# MasterNode.net
KiCad netlist of a schematic drawn in EAGLE
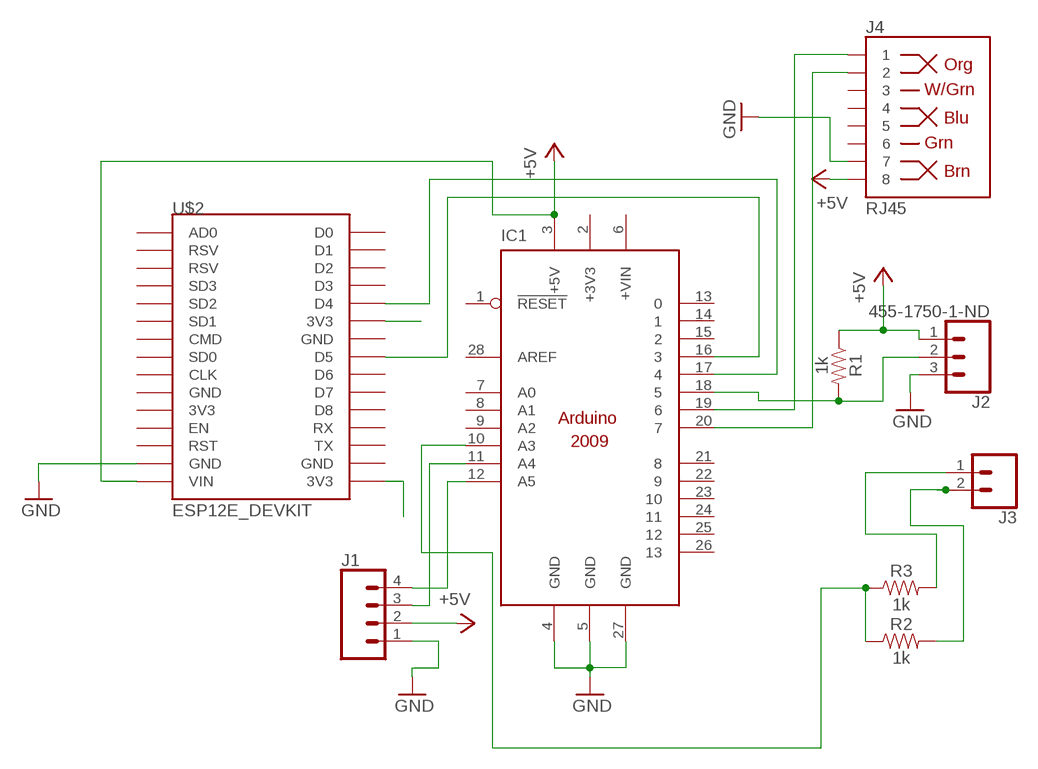
[diagram p0: schematic, sheet 1]

(export (version "E")
  (design (tool "Eeschema 10.0.6"))
  (components
    (comp (ref "IC1")
      (value "ARDUINO2009_10")
      (footprint "eagle-import:ARDUINO2009")
      (libsource (lib "eagle-import") (part "ARDUINO2009_10"))
    )
    (comp (ref "J1")
      (value "CONN_04PTH")
      (footprint "eagle-import:1X04")
      (libsource (lib "eagle-import") (part "CONN_04PTH"))
    )
    (comp (ref "J2")
      (value "455-1750-1-ND")
      (footprint "eagle-import:1X03")
      (libsource (lib "eagle-import") (part "CONN_03"))
    )
    (comp (ref "J3")
      (value "CONN_02")
      (footprint "eagle-import:1X02")
      (libsource (lib "eagle-import") (part "CONN_02"))
    )
    (comp (ref "J4")
      (value "RJ45")
      (footprint "eagle-import:RJ45-8")
      (libsource (lib "eagle-import") (part "RJ45-8"))
    )
    (comp (ref "R1")
      (value "1k")
      (footprint "eagle-import:AXIAL-0.3")
      (libsource (lib "eagle-import") (part "1KOHM-HORIZ-1/4W-5%"))
    )
    (comp (ref "R2")
      (value "1k")
      (footprint "eagle-import:AXIAL-0.3")
      (libsource (lib "eagle-import") (part "1KOHM-HORIZ-1/4W-5%"))
    )
    (comp (ref "R3")
      (value "1k")
      (footprint "eagle-import:AXIAL-0.3")
      (libsource (lib "eagle-import") (part "1KOHM-HORIZ-1/4W-5%"))
    )
    (comp (ref "U$2")
      (value "ESP12E_DEVKIT")
      (footprint "eagle-import:ESP12E_DEVKIT")
      (libsource (lib "eagle-import") (part "ESP12E_DEVKIT"))
    )
  )
  (nets
    (net (code "1") (name "+5V") (class "Default")
      (node (ref "IC1") (pin "3") (pinfunction "+5V_3") (pintype "power_in"))
      (node (ref "J1") (pin "2") (pinfunction "2_2") (pintype "passive"))
      (node (ref "J2") (pin "1") (pinfunction "1_1") (pintype "passive"))
      (node (ref "J4") (pin "8") (pinfunction "8_8") (pintype "bidirectional"))
      (node (ref "R1") (pin "P$1") (pinfunction "1_P$1") (pintype "passive"))
      (node (ref "U$2") (pin "VIN") (pinfunction "VIN_VIN") (pintype "bidirectional"))
    )
    (net (code "2") (name "/+3V3") (class "Default")
      (node (ref "IC1") (pin "2") (pinfunction "+3V3_2") (pintype "power_in"))
    )
    (net (code "3") (name "GND") (class "Default")
      (node (ref "IC1") (pin "27") (pinfunction "GND_27") (pintype "power_in"))
      (node (ref "IC1") (pin "4") (pinfunction "GND_4") (pintype "power_in"))
      (node (ref "IC1") (pin "5") (pinfunction "GND_5") (pintype "power_in"))
      (node (ref "J1") (pin "1") (pinfunction "1_1") (pintype "passive"))
      (node (ref "J2") (pin "3") (pinfunction "3_3") (pintype "passive"))
      (node (ref "J4") (pin "7") (pinfunction "7_7") (pintype "bidirectional"))
      (node (ref "U$2") (pin "GND@1") (pinfunction "GND_GND@1") (pintype "bidirectional"))
    )
    (net (code "4") (name "Net-(IC1-3)") (class "Default")
      (node (ref "IC1") (pin "16") (pinfunction "3_16") (pintype "bidirectional"))
      (node (ref "U$2") (pin "D5") (pinfunction "D5_D5") (pintype "bidirectional"))
    )
    (net (code "5") (name "Net-(IC1-4)") (class "Default")
      (node (ref "IC1") (pin "17") (pinfunction "4_17") (pintype "bidirectional"))
      (node (ref "U$2") (pin "D4") (pinfunction "D4_D4") (pintype "bidirectional"))
    )
    (net (code "6") (name "Net-(IC1-5)") (class "Default")
      (node (ref "IC1") (pin "18") (pinfunction "5_18") (pintype "bidirectional"))
      (node (ref "J2") (pin "2") (pinfunction "2_2") (pintype "passive"))
      (node (ref "R1") (pin "P$2") (pinfunction "2_P$2") (pintype "passive"))
    )
    (net (code "7") (name "Net-(IC1-6)") (class "Default")
      (node (ref "IC1") (pin "19") (pinfunction "6_19") (pintype "bidirectional"))
      (node (ref "J4") (pin "1") (pinfunction "1_1") (pintype "bidirectional"))
    )
    (net (code "8") (name "Net-(IC1-7)") (class "Default")
      (node (ref "IC1") (pin "20") (pinfunction "7_20") (pintype "bidirectional"))
      (node (ref "J4") (pin "2") (pinfunction "2_2") (pintype "bidirectional"))
    )
    (net (code "9") (name "Net-(IC1-A3)") (class "Default")
      (node (ref "IC1") (pin "10") (pinfunction "A3_10") (pintype "bidirectional"))
      (node (ref "R2") (pin "P$1") (pinfunction "1_P$1") (pintype "passive"))
      (node (ref "R3") (pin "P$1") (pinfunction "1_P$1") (pintype "passive"))
    )
    (net (code "10") (name "Net-(IC1-A4)") (class "Default")
      (node (ref "IC1") (pin "11") (pinfunction "A4_11") (pintype "bidirectional"))
      (node (ref "J1") (pin "3") (pinfunction "3_3") (pintype "passive"))
    )
    (net (code "11") (name "Net-(IC1-A5)") (class "Default")
      (node (ref "IC1") (pin "12") (pinfunction "A5_12") (pintype "bidirectional"))
      (node (ref "J1") (pin "4") (pinfunction "4_4") (pintype "passive"))
    )
    (net (code "12") (name "Net-(R2-2)") (class "Default")
      (node (ref "J3") (pin "2") (pinfunction "2_2") (pintype "passive"))
      (node (ref "R2") (pin "P$2") (pinfunction "2_P$2") (pintype "passive"))
    )
    (net (code "13") (name "Net-(R3-2)") (class "Default")
      (node (ref "J3") (pin "1") (pinfunction "1_1") (pintype "passive"))
      (node (ref "R3") (pin "P$2") (pinfunction "2_P$2") (pintype "passive"))
    )
    (net (code "14") (name "unconnected-(IC1-+VIN-Pad6)") (class "Default")
      (node (ref "IC1") (pin "6") (pinfunction "+VIN_6") (pintype "bidirectional"))
    )
    (net (code "15") (name "unconnected-(IC1-0-Pad13)") (class "Default")
      (node (ref "IC1") (pin "13") (pinfunction "0_13") (pintype "bidirectional"))
    )
    (net (code "16") (name "unconnected-(IC1-1-Pad14)") (class "Default")
      (node (ref "IC1") (pin "14") (pinfunction "1_14") (pintype "bidirectional"))
    )
    (net (code "17") (name "unconnected-(IC1-2-Pad15)") (class "Default")
      (node (ref "IC1") (pin "15") (pinfunction "2_15") (pintype "bidirectional"))
    )
    (net (code "18") (name "unconnected-(IC1-8-Pad21)") (class "Default")
      (node (ref "IC1") (pin "21") (pinfunction "8_21") (pintype "bidirectional"))
    )
    (net (code "19") (name "unconnected-(IC1-9-Pad22)") (class "Default")
      (node (ref "IC1") (pin "22") (pinfunction "9_22") (pintype "bidirectional"))
    )
    (net (code "20") (name "unconnected-(IC1-10-Pad23)") (class "Default")
      (node (ref "IC1") (pin "23") (pinfunction "10_23") (pintype "bidirectional"))
    )
    (net (code "21") (name "unconnected-(IC1-11-Pad24)") (class "Default")
      (node (ref "IC1") (pin "24") (pinfunction "11_24") (pintype "bidirectional"))
    )
    (net (code "22") (name "unconnected-(IC1-12-Pad25)") (class "Default")
      (node (ref "IC1") (pin "25") (pinfunction "12_25") (pintype "bidirectional"))
    )
    (net (code "23") (name "unconnected-(IC1-13-Pad26)") (class "Default")
      (node (ref "IC1") (pin "26") (pinfunction "13_26") (pintype "bidirectional"))
    )
    (net (code "24") (name "unconnected-(IC1-A0-Pad7)") (class "Default")
      (node (ref "IC1") (pin "7") (pinfunction "A0_7") (pintype "bidirectional"))
    )
    (net (code "25") (name "unconnected-(IC1-A1-Pad8)") (class "Default")
      (node (ref "IC1") (pin "8") (pinfunction "A1_8") (pintype "bidirectional"))
    )
    (net (code "26") (name "unconnected-(IC1-A2-Pad9)") (class "Default")
      (node (ref "IC1") (pin "9") (pinfunction "A2_9") (pintype "bidirectional"))
    )
    (net (code "27") (name "unconnected-(IC1-AREF-Pad28)") (class "Default")
      (node (ref "IC1") (pin "28") (pinfunction "AREF_28") (pintype "bidirectional"))
    )
    (net (code "28") (name "unconnected-(IC1-~{RESET}-Pad1)") (class "Default")
      (node (ref "IC1") (pin "1") (pinfunction "~{RESET}_1") (pintype "bidirectional"))
    )
    (net (code "29") (name "unconnected-(J4-Pad3)") (class "Default")
      (node (ref "J4") (pin "3") (pinfunction "3_3") (pintype "bidirectional"))
    )
    (net (code "30") (name "unconnected-(J4-Pad4)") (class "Default")
      (node (ref "J4") (pin "4") (pinfunction "4_4") (pintype "bidirectional"))
    )
    (net (code "31") (name "unconnected-(J4-Pad5)") (class "Default")
      (node (ref "J4") (pin "5") (pinfunction "5_5") (pintype "bidirectional"))
    )
    (net (code "32") (name "unconnected-(J4-Pad6)") (class "Default")
      (node (ref "J4") (pin "6") (pinfunction "6_6") (pintype "bidirectional"))
    )
    (net (code "33") (name "unconnected-(U$2-3V3-Pad3V3@0)") (class "Default")
      (node (ref "U$2") (pin "3V3@0") (pinfunction "3V3_3V3@0") (pintype "bidirectional"))
    )
    (net (code "34") (name "unconnected-(U$2-3V3-Pad3V3@1)") (class "Default")
      (node (ref "U$2") (pin "3V3@1") (pinfunction "3V3_3V3@1") (pintype "bidirectional"))
    )
    (net (code "35") (name "unconnected-(U$2-3V3-Pad3V3@2)") (class "Default")
      (node (ref "U$2") (pin "3V3@2") (pinfunction "3V3_3V3@2") (pintype "bidirectional"))
    )
    (net (code "36") (name "unconnected-(U$2-GND-PadGND@0)") (class "Default")
      (node (ref "U$2") (pin "GND@0") (pinfunction "GND_GND@0") (pintype "bidirectional"))
    )
    (net (code "37") (name "unconnected-(U$2-GND-PadGND@2)") (class "Default")
      (node (ref "U$2") (pin "GND@2") (pinfunction "GND_GND@2") (pintype "bidirectional"))
    )
    (net (code "38") (name "unconnected-(U$2-GND-PadGND@3)") (class "Default")
      (node (ref "U$2") (pin "GND@3") (pinfunction "GND_GND@3") (pintype "bidirectional"))
    )
    (net (code "39") (name "unconnected-(U$2-PadAD0)") (class "Default")
      (node (ref "U$2") (pin "AD0") (pinfunction "AD0_AD0") (pintype "bidirectional"))
    )
    (net (code "40") (name "unconnected-(U$2-PadCLK)") (class "Default")
      (node (ref "U$2") (pin "CLK") (pinfunction "CLK_CLK") (pintype "bidirectional"))
    )
    (net (code "41") (name "unconnected-(U$2-PadCMD)") (class "Default")
      (node (ref "U$2") (pin "CMD") (pinfunction "CMD_CMD") (pintype "bidirectional"))
    )
    (net (code "42") (name "unconnected-(U$2-PadD0)") (class "Default")
      (node (ref "U$2") (pin "D0") (pinfunction "D0_D0") (pintype "bidirectional"))
    )
    (net (code "43") (name "unconnected-(U$2-PadD1)") (class "Default")
      (node (ref "U$2") (pin "D1") (pinfunction "D1_D1") (pintype "bidirectional"))
    )
    (net (code "44") (name "unconnected-(U$2-PadD2)") (class "Default")
      (node (ref "U$2") (pin "D2") (pinfunction "D2_D2") (pintype "bidirectional"))
    )
    (net (code "45") (name "unconnected-(U$2-PadD3)") (class "Default")
      (node (ref "U$2") (pin "D3") (pinfunction "D3_D3") (pintype "bidirectional"))
    )
    (net (code "46") (name "unconnected-(U$2-PadD6)") (class "Default")
      (node (ref "U$2") (pin "D6") (pinfunction "D6_D6") (pintype "bidirectional"))
    )
    (net (code "47") (name "unconnected-(U$2-PadD7)") (class "Default")
      (node (ref "U$2") (pin "D7") (pinfunction "D7_D7") (pintype "bidirectional"))
    )
    (net (code "48") (name "unconnected-(U$2-PadD8)") (class "Default")
      (node (ref "U$2") (pin "D8") (pinfunction "D8_D8") (pintype "bidirectional"))
    )
    (net (code "49") (name "unconnected-(U$2-PadEN)") (class "Default")
      (node (ref "U$2") (pin "EN") (pinfunction "EN_EN") (pintype "bidirectional"))
    )
    (net (code "50") (name "unconnected-(U$2-PadRST)") (class "Default")
      (node (ref "U$2") (pin "RST") (pinfunction "RST_RST") (pintype "bidirectional"))
    )
    (net (code "51") (name "unconnected-(U$2-PadRX)") (class "Default")
      (node (ref "U$2") (pin "RX") (pinfunction "RX_RX") (pintype "bidirectional"))
    )
    (net (code "52") (name "unconnected-(U$2-PadSD0)") (class "Default")
      (node (ref "U$2") (pin "SD0") (pinfunction "SD0_SD0") (pintype "bidirectional"))
    )
    (net (code "53") (name "unconnected-(U$2-PadSD1)") (class "Default")
      (node (ref "U$2") (pin "SD1") (pinfunction "SD1_SD1") (pintype "bidirectional"))
    )
    (net (code "54") (name "unconnected-(U$2-PadSD2)") (class "Default")
      (node (ref "U$2") (pin "SD2") (pinfunction "SD2_SD2") (pintype "bidirectional"))
    )
    (net (code "55") (name "unconnected-(U$2-PadSD3)") (class "Default")
      (node (ref "U$2") (pin "SD3") (pinfunction "SD3_SD3") (pintype "bidirectional"))
    )
    (net (code "56") (name "unconnected-(U$2-PadTX)") (class "Default")
      (node (ref "U$2") (pin "TX") (pinfunction "TX_TX") (pintype "bidirectional"))
    )
    (net (code "57") (name "unconnected-(U$2-RSV-PadRSV@0)") (class "Default")
      (node (ref "U$2") (pin "RSV@0") (pinfunction "RSV_RSV@0") (pintype "bidirectional"))
    )
    (net (code "58") (name "unconnected-(U$2-RSV-PadRSV@1)") (class "Default")
      (node (ref "U$2") (pin "RSV@1") (pinfunction "RSV_RSV@1") (pintype "bidirectional"))
    )
  )
)
